# ESP32.net
KiCad netlist of a schematic drawn in Altium Designer
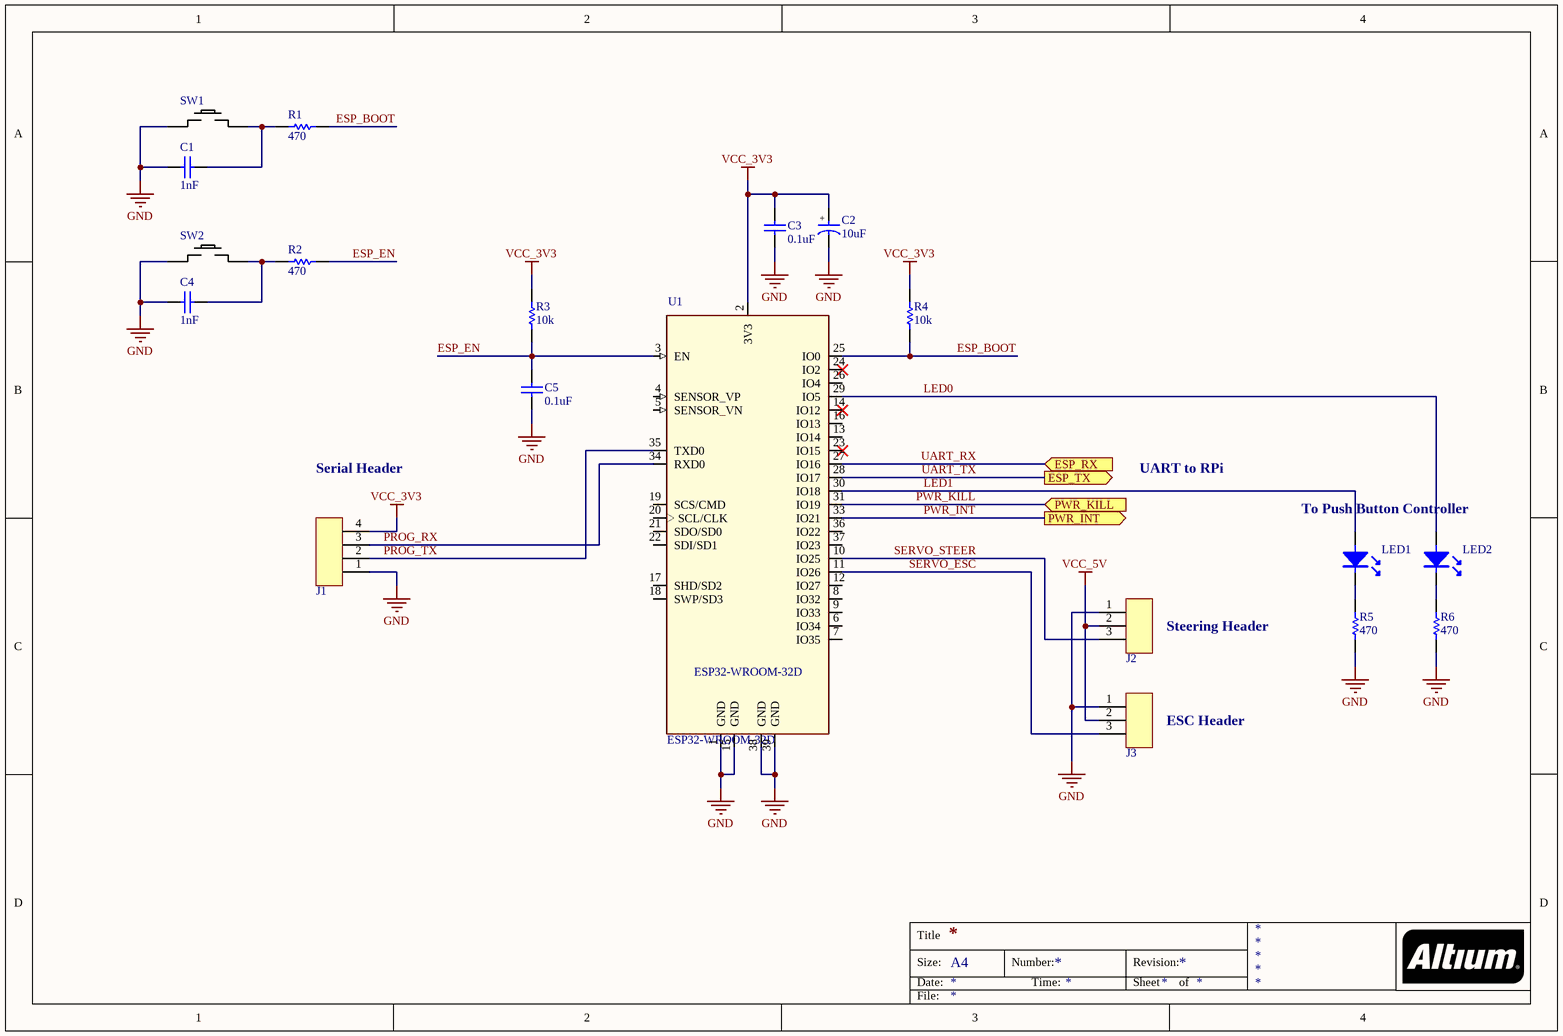
[diagram p0: ESP32.SchDoc]

(export (version "E")
  (design (tool "Eeschema 10.0.6"))
  (components
    (comp (ref "C1")
      (value "1nF")
      (footprint "C0603")
      (description "=Description")
      (fields (field (name "Comment") "CAP"))
      (libsource (lib "DRClib") (part "CAP"))
    )
    (comp (ref "C2")
      (value "10uF")
      (footprint "CASE-A")
      (description "=Description")
      (fields (field (name "Comment") "CAP-P"))
      (libsource (lib "DRClib") (part "CAP-P"))
    )
    (comp (ref "C3")
      (value "0.1uF")
      (footprint "C0603")
      (description "=Description")
      (fields (field (name "VOLTAGE") "25V") (field (name "Comment") "CAP"))
      (libsource (lib "DRClib") (part "CAP"))
    )
    (comp (ref "C4")
      (value "1nF")
      (footprint "C0603")
      (description "=Description")
      (fields (field (name "Comment") "CAP"))
      (libsource (lib "DRClib") (part "CAP"))
    )
    (comp (ref "C5")
      (value "0.1uF")
      (footprint "C0603")
      (description "=Description")
      (fields (field (name "VOLTAGE") "25V") (field (name "Comment") "CAP"))
      (libsource (lib "DRClib") (part "CAP"))
    )
    (comp (ref "J1")
      (value "HDR_1x4")
      (footprint "PINHEAD_2.54mm_1x4")
      (description "=Description")
      (libsource (lib "Header") (part "HDR_1x4"))
    )
    (comp (ref "J2")
      (value "HDR_1x3")
      (footprint "PINHEAD_2.54mm_1x3")
      (description "=Description")
      (libsource (lib "Header") (part "HDR_1x3"))
    )
    (comp (ref "J3")
      (value "HDR_1x3")
      (footprint "PINHEAD_2.54mm_1x3")
      (description "=Description")
      (libsource (lib "Header") (part "HDR_1x3"))
    )
    (comp (ref "LED1")
      (value "LED")
      (footprint "0603-LED")
      (fields (field (name "PART_NUMBER") "150060RS75000"))
      (libsource (lib "DRClib") (part "LED"))
    )
    (comp (ref "LED2")
      (value "LED")
      (footprint "0603-LED")
      (fields (field (name "PART_NUMBER") "150060RS75000"))
      (libsource (lib "DRClib") (part "LED"))
    )
    (comp (ref "R1")
      (value "470")
      (footprint "R0603")
      (description "=Description")
      (fields (field (name "Comment") "RES"))
      (libsource (lib "DRClib") (part "RES"))
    )
    (comp (ref "R2")
      (value "470")
      (footprint "R0603")
      (description "=Description")
      (fields (field (name "Comment") "RES"))
      (libsource (lib "DRClib") (part "RES"))
    )
    (comp (ref "R3")
      (value "10k")
      (footprint "R0603")
      (description "=Description")
      (fields (field (name "Comment") "RES"))
      (libsource (lib "DRClib") (part "RES"))
    )
    (comp (ref "R4")
      (value "10k")
      (footprint "R0603")
      (description "=Description")
      (fields (field (name "Comment") "RES"))
      (libsource (lib "DRClib") (part "RES"))
    )
    (comp (ref "R5")
      (value "470")
      (footprint "R0603")
      (description "=Description")
      (fields (field (name "Comment") "RES"))
      (libsource (lib "DRClib") (part "RES"))
    )
    (comp (ref "R6")
      (value "470")
      (footprint "R0603")
      (description "=Description")
      (fields (field (name "Comment") "RES"))
      (libsource (lib "DRClib") (part "RES"))
    )
    (comp (ref "SW1")
      (value "TACTILE_BUTTON")
      (footprint "TACTILE_BUTTOn")
      (libsource (lib "DRClib") (part "TACTILE_BUTTON"))
    )
    (comp (ref "SW2")
      (value "TACTILE_BUTTON")
      (footprint "TACTILE_BUTTOn")
      (libsource (lib "DRClib") (part "TACTILE_BUTTON"))
    )
    (comp (ref "U1")
      (value "ESP32-WROOM-32D")
      (footprint "ESP32-WROOM-32D")
      (description "IC: SoC; GPIO, I2C, I2S, IR, SD, SDIO, SPI, UART; 2.7Ã·3.6VDC; 20dBm")
      (fields (field (name "MF") "Espressif Systems") (field (name "PART_NUMBER") "ESP-WROOM-32D"))
      (libsource (lib "DRClib") (part "ESP32-WROOM-32D"))
    )
  )
  (nets
    (net (code "1") (name "/ESP_BOOT") (class "Default")
      (node (ref "R1") (pin "2") (pinfunction "2_2") (pintype "passive"))
      (node (ref "R4") (pin "2") (pinfunction "2_2") (pintype "passive"))
      (node (ref "U1") (pin "25") (pinfunction "IO0_25") (pintype "bidirectional"))
    )
    (net (code "2") (name "/ESP_EN") (class "Default")
      (node (ref "C5") (pin "1") (pinfunction "1_1") (pintype "passive"))
      (node (ref "R2") (pin "2") (pinfunction "2_2") (pintype "passive"))
      (node (ref "R3") (pin "2") (pinfunction "2_2") (pintype "passive"))
      (node (ref "U1") (pin "3") (pinfunction "EN_3") (pintype "input"))
    )
    (net (code "3") (name "/LED0") (class "Default")
      (node (ref "LED2") (pin "A") (pintype "passive"))
      (node (ref "U1") (pin "29") (pinfunction "IO5_29") (pintype "bidirectional"))
    )
    (net (code "4") (name "/LED1") (class "Default")
      (node (ref "LED1") (pin "A") (pintype "passive"))
      (node (ref "U1") (pin "30") (pinfunction "IO18_30") (pintype "bidirectional"))
    )
    (net (code "5") (name "/PROG_RX") (class "Default")
      (node (ref "J1") (pin "3") (pinfunction "3_3") (pintype "passive"))
      (node (ref "U1") (pin "34") (pinfunction "RXD0_34") (pintype "bidirectional"))
    )
    (net (code "6") (name "/PROG_TX") (class "Default")
      (node (ref "J1") (pin "2") (pinfunction "2_2") (pintype "passive"))
      (node (ref "U1") (pin "35") (pinfunction "TXD0_35") (pintype "bidirectional"))
    )
    (net (code "7") (name "/PWR_INT") (class "Default")
      (node (ref "U1") (pin "33") (pinfunction "IO21_33") (pintype "bidirectional"))
    )
    (net (code "8") (name "/PWR_KILL") (class "Default")
      (node (ref "U1") (pin "31") (pinfunction "IO19_31") (pintype "bidirectional"))
    )
    (net (code "9") (name "/SERVO_ESC") (class "Default")
      (node (ref "J3") (pin "3") (pinfunction "3_3") (pintype "passive"))
      (node (ref "U1") (pin "11") (pinfunction "IO26_11") (pintype "bidirectional"))
    )
    (net (code "10") (name "/SERVO_STEER") (class "Default")
      (node (ref "J2") (pin "3") (pinfunction "3_3") (pintype "passive"))
      (node (ref "U1") (pin "10") (pinfunction "IO25_10") (pintype "bidirectional"))
    )
    (net (code "11") (name "/UART_RX") (class "Default")
      (node (ref "U1") (pin "27") (pinfunction "IO16_27") (pintype "bidirectional"))
    )
    (net (code "12") (name "/UART_TX") (class "Default")
      (node (ref "U1") (pin "28") (pinfunction "IO17_28") (pintype "bidirectional"))
    )
    (net (code "13") (name "GND") (class "Default")
      (node (ref "C1") (pin "1") (pinfunction "1_1") (pintype "passive"))
      (node (ref "C2") (pin "2") (pinfunction "2_2") (pintype "passive"))
      (node (ref "C3") (pin "2") (pinfunction "2_2") (pintype "passive"))
      (node (ref "C4") (pin "1") (pinfunction "1_1") (pintype "passive"))
      (node (ref "C5") (pin "2") (pinfunction "2_2") (pintype "passive"))
      (node (ref "J1") (pin "1") (pinfunction "1_1") (pintype "passive"))
      (node (ref "J2") (pin "1") (pinfunction "1_1") (pintype "passive"))
      (node (ref "J3") (pin "1") (pinfunction "1_1") (pintype "passive"))
      (node (ref "R5") (pin "2") (pinfunction "2_2") (pintype "passive"))
      (node (ref "R6") (pin "2") (pinfunction "2_2") (pintype "passive"))
      (node (ref "SW1") (pin "1") (pinfunction "1_1") (pintype "passive"))
      (node (ref "SW2") (pin "1") (pinfunction "1_1") (pintype "passive"))
      (node (ref "U1") (pin "1") (pinfunction "GND_1") (pintype "power_in"))
      (node (ref "U1") (pin "15") (pinfunction "GND_15") (pintype "power_in"))
      (node (ref "U1") (pin "38") (pinfunction "GND_38") (pintype "power_in"))
      (node (ref "U1") (pin "39") (pinfunction "GND_39") (pintype "power_in"))
    )
    (net (code "14") (name "Net-(C1-Pad2)") (class "Default")
      (node (ref "C1") (pin "2") (pinfunction "2_2") (pintype "passive"))
      (node (ref "R1") (pin "1") (pinfunction "1_1") (pintype "passive"))
      (node (ref "SW1") (pin "2") (pinfunction "1_2") (pintype "passive"))
    )
    (net (code "15") (name "Net-(C4-Pad2)") (class "Default")
      (node (ref "C4") (pin "2") (pinfunction "2_2") (pintype "passive"))
      (node (ref "R2") (pin "1") (pinfunction "1_1") (pintype "passive"))
      (node (ref "SW2") (pin "2") (pinfunction "1_2") (pintype "passive"))
    )
    (net (code "16") (name "Net-(LED1-PadK)") (class "Default")
      (node (ref "LED1") (pin "K") (pintype "passive"))
      (node (ref "R5") (pin "1") (pinfunction "1_1") (pintype "passive"))
    )
    (net (code "17") (name "Net-(LED2-PadK)") (class "Default")
      (node (ref "LED2") (pin "K") (pintype "passive"))
      (node (ref "R6") (pin "1") (pinfunction "1_1") (pintype "passive"))
    )
    (net (code "18") (name "VCC_3V3") (class "Default")
      (node (ref "C2") (pin "1") (pinfunction "1_1") (pintype "passive"))
      (node (ref "C3") (pin "1") (pinfunction "1_1") (pintype "passive"))
      (node (ref "J1") (pin "4") (pinfunction "4_4") (pintype "passive"))
      (node (ref "R3") (pin "1") (pinfunction "1_1") (pintype "passive"))
      (node (ref "R4") (pin "1") (pinfunction "1_1") (pintype "passive"))
      (node (ref "U1") (pin "2") (pinfunction "3V3_2") (pintype "power_in"))
    )
    (net (code "19") (name "VCC_5V") (class "Default")
      (node (ref "J2") (pin "2") (pinfunction "2_2") (pintype "passive"))
      (node (ref "J3") (pin "2") (pinfunction "2_2") (pintype "passive"))
    )
    (net (code "20") (name "unconnected-(U1-IO2-Pad24)") (class "Default")
      (node (ref "U1") (pin "24") (pinfunction "IO2_24") (pintype "bidirectional+no_connect"))
    )
    (net (code "21") (name "unconnected-(U1-IO4-Pad26)") (class "Default")
      (node (ref "U1") (pin "26") (pinfunction "IO4_26") (pintype "bidirectional"))
    )
    (net (code "22") (name "unconnected-(U1-IO12-Pad14)") (class "Default")
      (node (ref "U1") (pin "14") (pinfunction "IO12_14") (pintype "bidirectional+no_connect"))
    )
    (net (code "23") (name "unconnected-(U1-IO13-Pad16)") (class "Default")
      (node (ref "U1") (pin "16") (pinfunction "IO13_16") (pintype "bidirectional"))
    )
    (net (code "24") (name "unconnected-(U1-IO14-Pad13)") (class "Default")
      (node (ref "U1") (pin "13") (pinfunction "IO14_13") (pintype "bidirectional"))
    )
    (net (code "25") (name "unconnected-(U1-IO15-Pad23)") (class "Default")
      (node (ref "U1") (pin "23") (pinfunction "IO15_23") (pintype "bidirectional+no_connect"))
    )
    (net (code "26") (name "unconnected-(U1-IO22-Pad36)") (class "Default")
      (node (ref "U1") (pin "36") (pinfunction "IO22_36") (pintype "bidirectional"))
    )
    (net (code "27") (name "unconnected-(U1-IO23-Pad37)") (class "Default")
      (node (ref "U1") (pin "37") (pinfunction "IO23_37") (pintype "bidirectional"))
    )
    (net (code "28") (name "unconnected-(U1-IO27-Pad12)") (class "Default")
      (node (ref "U1") (pin "12") (pinfunction "IO27_12") (pintype "bidirectional"))
    )
    (net (code "29") (name "unconnected-(U1-IO32-Pad8)") (class "Default")
      (node (ref "U1") (pin "8") (pinfunction "IO32_8") (pintype "bidirectional"))
    )
    (net (code "30") (name "unconnected-(U1-IO33-Pad9)") (class "Default")
      (node (ref "U1") (pin "9") (pinfunction "IO33_9") (pintype "bidirectional"))
    )
    (net (code "31") (name "unconnected-(U1-IO34-Pad6)") (class "Default")
      (node (ref "U1") (pin "6") (pinfunction "IO34_6") (pintype "bidirectional"))
    )
    (net (code "32") (name "unconnected-(U1-IO35-Pad7)") (class "Default")
      (node (ref "U1") (pin "7") (pinfunction "IO35_7") (pintype "bidirectional"))
    )
    (net (code "33") (name "unconnected-(U1-SCL{slash}CLK-Pad20)") (class "Default")
      (node (ref "U1") (pin "20") (pinfunction "SCL/CLK_20") (pintype "bidirectional"))
    )
    (net (code "34") (name "unconnected-(U1-SCS{slash}CMD-Pad19)") (class "Default")
      (node (ref "U1") (pin "19") (pinfunction "SCS/CMD_19") (pintype "bidirectional"))
    )
    (net (code "35") (name "unconnected-(U1-SDI{slash}SD1-Pad22)") (class "Default")
      (node (ref "U1") (pin "22") (pinfunction "SDI/SD1_22") (pintype "bidirectional"))
    )
    (net (code "36") (name "unconnected-(U1-SDO{slash}SD0-Pad21)") (class "Default")
      (node (ref "U1") (pin "21") (pinfunction "SDO/SD0_21") (pintype "bidirectional"))
    )
    (net (code "37") (name "unconnected-(U1-SENSOR_VN-Pad5)") (class "Default")
      (node (ref "U1") (pin "5") (pinfunction "SENSOR_VN_5") (pintype "input"))
    )
    (net (code "38") (name "unconnected-(U1-SENSOR_VP-Pad4)") (class "Default")
      (node (ref "U1") (pin "4") (pinfunction "SENSOR_VP_4") (pintype "input"))
    )
    (net (code "39") (name "unconnected-(U1-SHD{slash}SD2-Pad17)") (class "Default")
      (node (ref "U1") (pin "17") (pinfunction "SHD/SD2_17") (pintype "bidirectional"))
    )
    (net (code "40") (name "unconnected-(U1-SWP{slash}SD3-Pad18)") (class "Default")
      (node (ref "U1") (pin "18") (pinfunction "SWP/SD3_18") (pintype "bidirectional"))
    )
  )
)
